# A7_FUNCTION3.net
KiCad netlist of a schematic drawn in Altium Designer
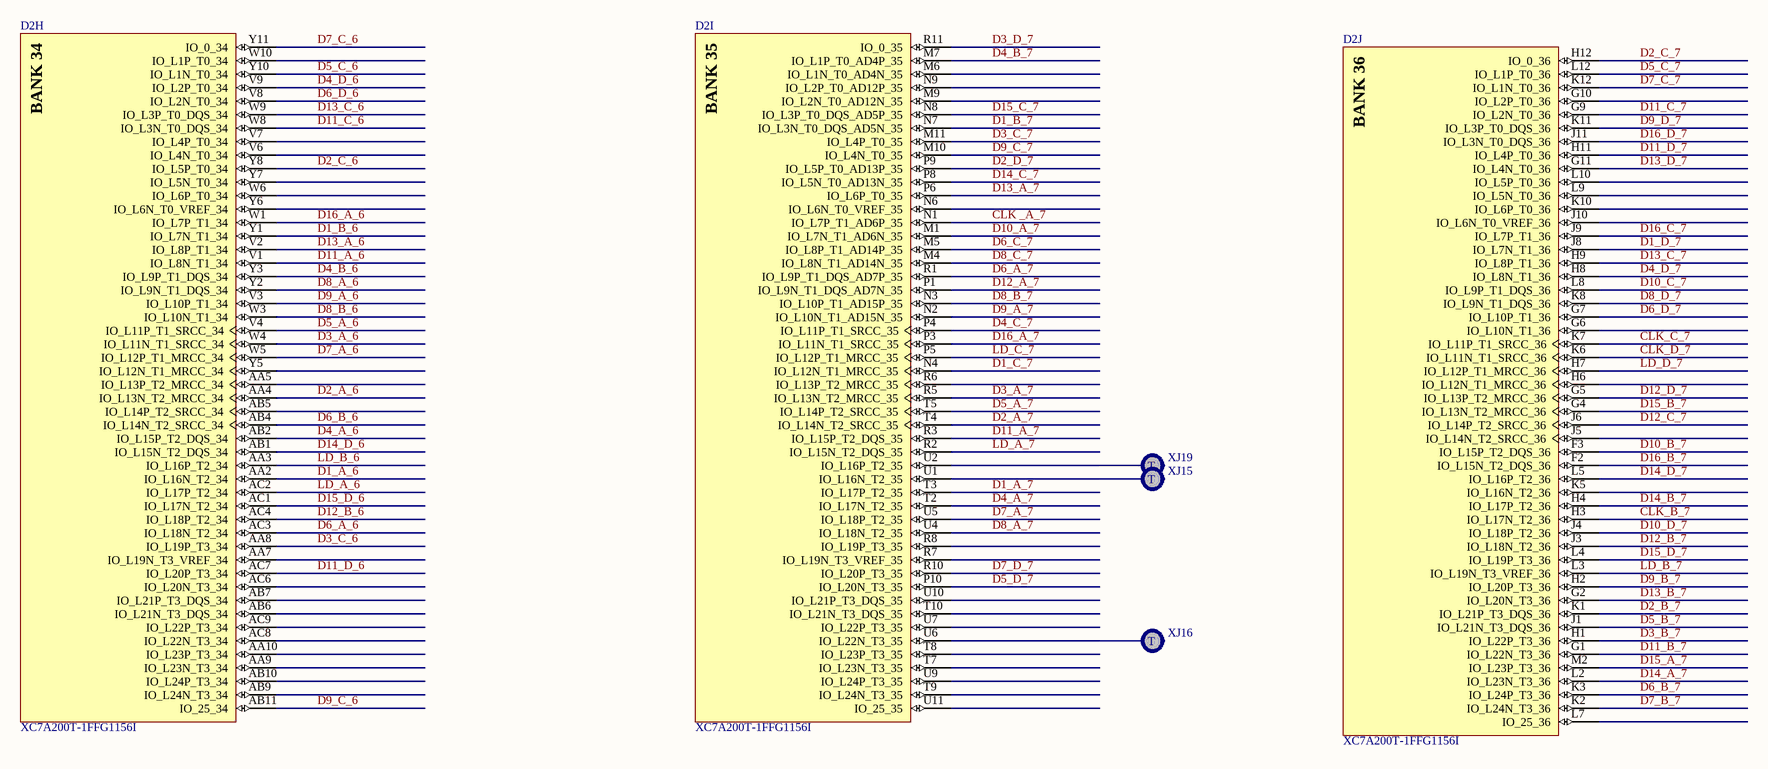
[diagram p0: A7_FUNCTION3.SchDoc]

(export (version "E")
  (design (tool "Eeschema 10.0.6"))
  (components
    (comp (ref "D2")
      (value "XC7A200T-1FFG1156I")
      (footprint "FFG1156")
      (description "Artix-7 FPGA, 500 User I/Os, 16 GTP, 1156-Ball BGA, Speed Grade 1, Industrial Grade, Pb-Free")
      (fields (field (name "GENERIC PART NUMBER") "XC7A200T") (field (name "MANUFACTURER") "Xilinx"))
      (libsource (lib "Xilinx Artix-7") (part "XC7A200T-1FFG1156I"))
    )
    (comp (ref "XJ15")
      (value "TESTPOINT")
      (footprint "TEST-pin")
      (description "测试点")
      (libsource (lib "Database_Libs1") (part "TESTPOINT"))
    )
    (comp (ref "XJ16")
      (value "TESTPOINT")
      (footprint "TEST-pin")
      (description "测试点")
      (libsource (lib "Database_Libs1") (part "TESTPOINT"))
    )
    (comp (ref "XJ19")
      (value "TESTPOINT")
      (footprint "TEST-pin")
      (description "测试点")
      (libsource (lib "Database_Libs1") (part "TESTPOINT"))
    )
  )
  (nets
    (net (code "1") (name "/CLK _A_7") (class "Default")
      (node (ref "D2") (pin "N1") (pinfunction "IO_L7P_T1_AD6P_35_N1") (pintype "bidirectional"))
    )
    (net (code "2") (name "/CLK_B_7") (class "Default")
      (node (ref "D2") (pin "H3") (pinfunction "IO_L17N_T2_36_H3") (pintype "bidirectional"))
    )
    (net (code "3") (name "/CLK_C_7") (class "Default")
      (node (ref "D2") (pin "K7") (pinfunction "IO_L11P_T1_SRCC_36_K7") (pintype "bidirectional"))
    )
    (net (code "4") (name "/CLK_D_7") (class "Default")
      (node (ref "D2") (pin "K6") (pinfunction "IO_L11N_T1_SRCC_36_K6") (pintype "bidirectional"))
    )
    (net (code "5") (name "/D1_A_6") (class "Default")
      (node (ref "D2") (pin "AA2") (pinfunction "IO_L16N_T2_34_AA2") (pintype "bidirectional"))
    )
    (net (code "6") (name "/D1_A_7") (class "Default")
      (node (ref "D2") (pin "T3") (pinfunction "IO_L17P_T2_35_T3") (pintype "bidirectional"))
    )
    (net (code "7") (name "/D1_B_6") (class "Default")
      (node (ref "D2") (pin "Y1") (pinfunction "IO_L7N_T1_34_Y1") (pintype "bidirectional"))
    )
    (net (code "8") (name "/D1_B_7") (class "Default")
      (node (ref "D2") (pin "N7") (pinfunction "IO_L3N_T0_DQS_AD5N_35_N7") (pintype "bidirectional"))
    )
    (net (code "9") (name "/D1_C_7") (class "Default")
      (node (ref "D2") (pin "N4") (pinfunction "IO_L12N_T1_MRCC_35_N4") (pintype "bidirectional"))
    )
    (net (code "10") (name "/D1_D_7") (class "Default")
      (node (ref "D2") (pin "J8") (pinfunction "IO_L7N_T1_36_J8") (pintype "bidirectional"))
    )
    (net (code "11") (name "/D2_A_6") (class "Default")
      (node (ref "D2") (pin "AA4") (pinfunction "IO_L13N_T2_MRCC_34_AA4") (pintype "bidirectional"))
    )
    (net (code "12") (name "/D2_A_7") (class "Default")
      (node (ref "D2") (pin "T4") (pinfunction "IO_L14N_T2_SRCC_35_T4") (pintype "bidirectional"))
    )
    (net (code "13") (name "/D2_B_7") (class "Default")
      (node (ref "D2") (pin "K1") (pinfunction "IO_L21P_T3_DQS_36_K1") (pintype "bidirectional"))
    )
    (net (code "14") (name "/D2_C_6") (class "Default")
      (node (ref "D2") (pin "Y8") (pinfunction "IO_L5P_T0_34_Y8") (pintype "bidirectional"))
    )
    (net (code "15") (name "/D2_C_7") (class "Default")
      (node (ref "D2") (pin "H12") (pinfunction "IO_0_36_H12") (pintype "bidirectional"))
    )
    (net (code "16") (name "/D2_D_7") (class "Default")
      (node (ref "D2") (pin "P9") (pinfunction "IO_L5P_T0_AD13P_35_P9") (pintype "bidirectional"))
    )
    (net (code "17") (name "/D3_A_6") (class "Default")
      (node (ref "D2") (pin "W4") (pinfunction "IO_L11N_T1_SRCC_34_W4") (pintype "bidirectional"))
    )
    (net (code "18") (name "/D3_A_7") (class "Default")
      (node (ref "D2") (pin "R5") (pinfunction "IO_L13N_T2_MRCC_35_R5") (pintype "bidirectional"))
    )
    (net (code "19") (name "/D3_B_7") (class "Default")
      (node (ref "D2") (pin "H1") (pinfunction "IO_L22P_T3_36_H1") (pintype "bidirectional"))
    )
    (net (code "20") (name "/D3_C_6") (class "Default")
      (node (ref "D2") (pin "AA8") (pinfunction "IO_L19P_T3_34_AA8") (pintype "bidirectional"))
    )
    (net (code "21") (name "/D3_C_7") (class "Default")
      (node (ref "D2") (pin "M11") (pinfunction "IO_L4P_T0_35_M11") (pintype "bidirectional"))
    )
    (net (code "22") (name "/D3_D_7") (class "Default")
      (node (ref "D2") (pin "R11") (pinfunction "IO_0_35_R11") (pintype "bidirectional"))
    )
    (net (code "23") (name "/D4_A_6") (class "Default")
      (node (ref "D2") (pin "AB2") (pinfunction "IO_L15P_T2_DQS_34_AB2") (pintype "bidirectional"))
    )
    (net (code "24") (name "/D4_A_7") (class "Default")
      (node (ref "D2") (pin "T2") (pinfunction "IO_L17N_T2_35_T2") (pintype "bidirectional"))
    )
    (net (code "25") (name "/D4_B_6") (class "Default")
      (node (ref "D2") (pin "Y3") (pinfunction "IO_L9P_T1_DQS_34_Y3") (pintype "bidirectional"))
    )
    (net (code "26") (name "/D4_B_7") (class "Default")
      (node (ref "D2") (pin "M7") (pinfunction "IO_L1P_T0_AD4P_35_M7") (pintype "bidirectional"))
    )
    (net (code "27") (name "/D4_C_7") (class "Default")
      (node (ref "D2") (pin "P4") (pinfunction "IO_L11P_T1_SRCC_35_P4") (pintype "bidirectional"))
    )
    (net (code "28") (name "/D4_D_6") (class "Default")
      (node (ref "D2") (pin "V9") (pinfunction "IO_L2P_T0_34_V9") (pintype "bidirectional"))
    )
    (net (code "29") (name "/D4_D_7") (class "Default")
      (node (ref "D2") (pin "H8") (pinfunction "IO_L8N_T1_36_H8") (pintype "bidirectional"))
    )
    (net (code "30") (name "/D5_A_6") (class "Default")
      (node (ref "D2") (pin "V4") (pinfunction "IO_L11P_T1_SRCC_34_V4") (pintype "bidirectional"))
    )
    (net (code "31") (name "/D5_A_7") (class "Default")
      (node (ref "D2") (pin "T5") (pinfunction "IO_L14P_T2_SRCC_35_T5") (pintype "bidirectional"))
    )
    (net (code "32") (name "/D5_B_7") (class "Default")
      (node (ref "D2") (pin "J1") (pinfunction "IO_L21N_T3_DQS_36_J1") (pintype "bidirectional"))
    )
    (net (code "33") (name "/D5_C_6") (class "Default")
      (node (ref "D2") (pin "Y10") (pinfunction "IO_L1N_T0_34_Y10") (pintype "bidirectional"))
    )
    (net (code "34") (name "/D5_C_7") (class "Default")
      (node (ref "D2") (pin "L12") (pinfunction "IO_L1P_T0_36_L12") (pintype "bidirectional"))
    )
    (net (code "35") (name "/D5_D_7") (class "Default")
      (node (ref "D2") (pin "P10") (pinfunction "IO_L20N_T3_35_P10") (pintype "bidirectional"))
    )
    (net (code "36") (name "/D6_A_6") (class "Default")
      (node (ref "D2") (pin "AC3") (pinfunction "IO_L18N_T2_34_AC3") (pintype "bidirectional"))
    )
    (net (code "37") (name "/D6_A_7") (class "Default")
      (node (ref "D2") (pin "R1") (pinfunction "IO_L9P_T1_DQS_AD7P_35_R1") (pintype "bidirectional"))
    )
    (net (code "38") (name "/D6_B_6") (class "Default")
      (node (ref "D2") (pin "AB4") (pinfunction "IO_L14N_T2_SRCC_34_AB4") (pintype "bidirectional"))
    )
    (net (code "39") (name "/D6_B_7") (class "Default")
      (node (ref "D2") (pin "K3") (pinfunction "IO_L24P_T3_36_K3") (pintype "bidirectional"))
    )
    (net (code "40") (name "/D6_C_7") (class "Default")
      (node (ref "D2") (pin "M5") (pinfunction "IO_L8P_T1_AD14P_35_M5") (pintype "bidirectional"))
    )
    (net (code "41") (name "/D6_D_6") (class "Default")
      (node (ref "D2") (pin "V8") (pinfunction "IO_L2N_T0_34_V8") (pintype "bidirectional"))
    )
    (net (code "42") (name "/D6_D_7") (class "Default")
      (node (ref "D2") (pin "G7") (pinfunction "IO_L10P_T1_36_G7") (pintype "bidirectional"))
    )
    (net (code "43") (name "/D7_A_6") (class "Default")
      (node (ref "D2") (pin "W5") (pinfunction "IO_L12P_T1_MRCC_34_W5") (pintype "bidirectional"))
    )
    (net (code "44") (name "/D7_A_7") (class "Default")
      (node (ref "D2") (pin "U5") (pinfunction "IO_L18P_T2_35_U5") (pintype "bidirectional"))
    )
    (net (code "45") (name "/D7_B_7") (class "Default")
      (node (ref "D2") (pin "K2") (pinfunction "IO_L24N_T3_36_K2") (pintype "bidirectional"))
    )
    (net (code "46") (name "/D7_C_6") (class "Default")
      (node (ref "D2") (pin "Y11") (pinfunction "IO_0_34_Y11") (pintype "bidirectional"))
    )
    (net (code "47") (name "/D7_C_7") (class "Default")
      (node (ref "D2") (pin "K12") (pinfunction "IO_L1N_T0_36_K12") (pintype "bidirectional"))
    )
    (net (code "48") (name "/D7_D_7") (class "Default")
      (node (ref "D2") (pin "R10") (pinfunction "IO_L20P_T3_35_R10") (pintype "bidirectional"))
    )
    (net (code "49") (name "/D8_A_6") (class "Default")
      (node (ref "D2") (pin "Y2") (pinfunction "IO_L9N_T1_DQS_34_Y2") (pintype "bidirectional"))
    )
    (net (code "50") (name "/D8_A_7") (class "Default")
      (node (ref "D2") (pin "U4") (pinfunction "IO_L18N_T2_35_U4") (pintype "bidirectional"))
    )
    (net (code "51") (name "/D8_B_6") (class "Default")
      (node (ref "D2") (pin "W3") (pinfunction "IO_L10N_T1_34_W3") (pintype "bidirectional"))
    )
    (net (code "52") (name "/D8_B_7") (class "Default")
      (node (ref "D2") (pin "N3") (pinfunction "IO_L10P_T1_AD15P_35_N3") (pintype "bidirectional"))
    )
    (net (code "53") (name "/D8_C_7") (class "Default")
      (node (ref "D2") (pin "M4") (pinfunction "IO_L8N_T1_AD14N_35_M4") (pintype "bidirectional"))
    )
    (net (code "54") (name "/D8_D_7") (class "Default")
      (node (ref "D2") (pin "K8") (pinfunction "IO_L9N_T1_DQS_36_K8") (pintype "bidirectional"))
    )
    (net (code "55") (name "/D9_A_6") (class "Default")
      (node (ref "D2") (pin "V3") (pinfunction "IO_L10P_T1_34_V3") (pintype "bidirectional"))
    )
    (net (code "56") (name "/D9_A_7") (class "Default")
      (node (ref "D2") (pin "N2") (pinfunction "IO_L10N_T1_AD15N_35_N2") (pintype "bidirectional"))
    )
    (net (code "57") (name "/D9_B_7") (class "Default")
      (node (ref "D2") (pin "H2") (pinfunction "IO_L20P_T3_36_H2") (pintype "bidirectional"))
    )
    (net (code "58") (name "/D9_C_6") (class "Default")
      (node (ref "D2") (pin "AB11") (pinfunction "IO_25_34_AB11") (pintype "bidirectional"))
    )
    (net (code "59") (name "/D9_C_7") (class "Default")
      (node (ref "D2") (pin "M10") (pinfunction "IO_L4N_T0_35_M10") (pintype "bidirectional"))
    )
    (net (code "60") (name "/D9_D_7") (class "Default")
      (node (ref "D2") (pin "K11") (pinfunction "IO_L3P_T0_DQS_36_K11") (pintype "bidirectional"))
    )
    (net (code "61") (name "/D10_A_7") (class "Default")
      (node (ref "D2") (pin "M1") (pinfunction "IO_L7N_T1_AD6N_35_M1") (pintype "bidirectional"))
    )
    (net (code "62") (name "/D10_B_7") (class "Default")
      (node (ref "D2") (pin "F3") (pinfunction "IO_L15P_T2_DQS_36_F3") (pintype "bidirectional"))
    )
    (net (code "63") (name "/D10_C_7") (class "Default")
      (node (ref "D2") (pin "L8") (pinfunction "IO_L9P_T1_DQS_36_L8") (pintype "bidirectional"))
    )
    (net (code "64") (name "/D10_D_7") (class "Default")
      (node (ref "D2") (pin "J4") (pinfunction "IO_L18P_T2_36_J4") (pintype "bidirectional"))
    )
    (net (code "65") (name "/D11_A_6") (class "Default")
      (node (ref "D2") (pin "V1") (pinfunction "IO_L8N_T1_34_V1") (pintype "bidirectional"))
    )
    (net (code "66") (name "/D11_A_7") (class "Default")
      (node (ref "D2") (pin "R3") (pinfunction "IO_L15P_T2_DQS_35_R3") (pintype "bidirectional"))
    )
    (net (code "67") (name "/D11_B_7") (class "Default")
      (node (ref "D2") (pin "G1") (pinfunction "IO_L22N_T3_36_G1") (pintype "bidirectional"))
    )
    (net (code "68") (name "/D11_C_6") (class "Default")
      (node (ref "D2") (pin "W8") (pinfunction "IO_L3N_T0_DQS_34_W8") (pintype "bidirectional"))
    )
    (net (code "69") (name "/D11_C_7") (class "Default")
      (node (ref "D2") (pin "G9") (pinfunction "IO_L2N_T0_36_G9") (pintype "bidirectional"))
    )
    (net (code "70") (name "/D11_D_6") (class "Default")
      (node (ref "D2") (pin "AC7") (pinfunction "IO_L20P_T3_34_AC7") (pintype "bidirectional"))
    )
    (net (code "71") (name "/D11_D_7") (class "Default")
      (node (ref "D2") (pin "H11") (pinfunction "IO_L4P_T0_36_H11") (pintype "bidirectional"))
    )
    (net (code "72") (name "/D12_A_7") (class "Default")
      (node (ref "D2") (pin "P1") (pinfunction "IO_L9N_T1_DQS_AD7N_35_P1") (pintype "bidirectional"))
    )
    (net (code "73") (name "/D12_B_6") (class "Default")
      (node (ref "D2") (pin "AC4") (pinfunction "IO_L18P_T2_34_AC4") (pintype "bidirectional"))
    )
    (net (code "74") (name "/D12_B_7") (class "Default")
      (node (ref "D2") (pin "J3") (pinfunction "IO_L18N_T2_36_J3") (pintype "bidirectional"))
    )
    (net (code "75") (name "/D12_C_7") (class "Default")
      (node (ref "D2") (pin "J6") (pinfunction "IO_L14P_T2_SRCC_36_J6") (pintype "bidirectional"))
    )
    (net (code "76") (name "/D12_D_7") (class "Default")
      (node (ref "D2") (pin "G5") (pinfunction "IO_L13P_T2_MRCC_36_G5") (pintype "bidirectional"))
    )
    (net (code "77") (name "/D13_A_6") (class "Default")
      (node (ref "D2") (pin "V2") (pinfunction "IO_L8P_T1_34_V2") (pintype "bidirectional"))
    )
    (net (code "78") (name "/D13_A_7") (class "Default")
      (node (ref "D2") (pin "P6") (pinfunction "IO_L6P_T0_35_P6") (pintype "bidirectional"))
    )
    (net (code "79") (name "/D13_B_7") (class "Default")
      (node (ref "D2") (pin "G2") (pinfunction "IO_L20N_T3_36_G2") (pintype "bidirectional"))
    )
    (net (code "80") (name "/D13_C_6") (class "Default")
      (node (ref "D2") (pin "W9") (pinfunction "IO_L3P_T0_DQS_34_W9") (pintype "bidirectional"))
    )
    (net (code "81") (name "/D13_C_7") (class "Default")
      (node (ref "D2") (pin "H9") (pinfunction "IO_L8P_T1_36_H9") (pintype "bidirectional"))
    )
    (net (code "82") (name "/D13_D_7") (class "Default")
      (node (ref "D2") (pin "G11") (pinfunction "IO_L4N_T0_36_G11") (pintype "bidirectional"))
    )
    (net (code "83") (name "/D14_A_7") (class "Default")
      (node (ref "D2") (pin "L2") (pinfunction "IO_L23N_T3_36_L2") (pintype "bidirectional"))
    )
    (net (code "84") (name "/D14_B_7") (class "Default")
      (node (ref "D2") (pin "H4") (pinfunction "IO_L17P_T2_36_H4") (pintype "bidirectional"))
    )
    (net (code "85") (name "/D14_C_7") (class "Default")
      (node (ref "D2") (pin "P8") (pinfunction "IO_L5N_T0_AD13N_35_P8") (pintype "bidirectional"))
    )
    (net (code "86") (name "/D14_D_6") (class "Default")
      (node (ref "D2") (pin "AB1") (pinfunction "IO_L15N_T2_DQS_34_AB1") (pintype "bidirectional"))
    )
    (net (code "87") (name "/D14_D_7") (class "Default")
      (node (ref "D2") (pin "L5") (pinfunction "IO_L16P_T2_36_L5") (pintype "bidirectional"))
    )
    (net (code "88") (name "/D15_A_7") (class "Default")
      (node (ref "D2") (pin "M2") (pinfunction "IO_L23P_T3_36_M2") (pintype "bidirectional"))
    )
    (net (code "89") (name "/D15_B_7") (class "Default")
      (node (ref "D2") (pin "G4") (pinfunction "IO_L13N_T2_MRCC_36_G4") (pintype "bidirectional"))
    )
    (net (code "90") (name "/D15_C_7") (class "Default")
      (node (ref "D2") (pin "N8") (pinfunction "IO_L3P_T0_DQS_AD5P_35_N8") (pintype "bidirectional"))
    )
    (net (code "91") (name "/D15_D_6") (class "Default")
      (node (ref "D2") (pin "AC1") (pinfunction "IO_L17N_T2_34_AC1") (pintype "bidirectional"))
    )
    (net (code "92") (name "/D15_D_7") (class "Default")
      (node (ref "D2") (pin "L4") (pinfunction "IO_L19P_T3_36_L4") (pintype "bidirectional"))
    )
    (net (code "93") (name "/D16_A_6") (class "Default")
      (node (ref "D2") (pin "W1") (pinfunction "IO_L7P_T1_34_W1") (pintype "bidirectional"))
    )
    (net (code "94") (name "/D16_A_7") (class "Default")
      (node (ref "D2") (pin "P3") (pinfunction "IO_L11N_T1_SRCC_35_P3") (pintype "bidirectional"))
    )
    (net (code "95") (name "/D16_B_7") (class "Default")
      (node (ref "D2") (pin "F2") (pinfunction "IO_L15N_T2_DQS_36_F2") (pintype "bidirectional"))
    )
    (net (code "96") (name "/D16_C_7") (class "Default")
      (node (ref "D2") (pin "J9") (pinfunction "IO_L7P_T1_36_J9") (pintype "bidirectional"))
    )
    (net (code "97") (name "/D16_D_7") (class "Default")
      (node (ref "D2") (pin "J11") (pinfunction "IO_L3N_T0_DQS_36_J11") (pintype "bidirectional"))
    )
    (net (code "98") (name "/LD_A_6") (class "Default")
      (node (ref "D2") (pin "AC2") (pinfunction "IO_L17P_T2_34_AC2") (pintype "bidirectional"))
    )
    (net (code "99") (name "/LD_A_7") (class "Default")
      (node (ref "D2") (pin "R2") (pinfunction "IO_L15N_T2_DQS_35_R2") (pintype "bidirectional"))
    )
    (net (code "100") (name "/LD_B_6") (class "Default")
      (node (ref "D2") (pin "AA3") (pinfunction "IO_L16P_T2_34_AA3") (pintype "bidirectional"))
    )
    (net (code "101") (name "/LD_B_7") (class "Default")
      (node (ref "D2") (pin "L3") (pinfunction "IO_L19N_T3_VREF_36_L3") (pintype "bidirectional"))
    )
    (net (code "102") (name "/LD_C_7") (class "Default")
      (node (ref "D2") (pin "P5") (pinfunction "IO_L12P_T1_MRCC_35_P5") (pintype "bidirectional"))
    )
    (net (code "103") (name "/LD_D_7") (class "Default")
      (node (ref "D2") (pin "H7") (pinfunction "IO_L12P_T1_MRCC_36_H7") (pintype "bidirectional"))
    )
    (net (code "104") (name "Net-(D2I-IO_L16N_T2_35)") (class "Default")
      (node (ref "D2") (pin "U1") (pinfunction "IO_L16N_T2_35_U1") (pintype "bidirectional"))
      (node (ref "XJ15") (pin "1") (pinfunction "T_1") (pintype "passive"))
    )
    (net (code "105") (name "Net-(D2I-IO_L16P_T2_35)") (class "Default")
      (node (ref "D2") (pin "U2") (pinfunction "IO_L16P_T2_35_U2") (pintype "bidirectional"))
      (node (ref "XJ19") (pin "1") (pinfunction "T_1") (pintype "passive"))
    )
    (net (code "106") (name "Net-(D2I-IO_L22N_T3_35)") (class "Default")
      (node (ref "D2") (pin "U6") (pinfunction "IO_L22N_T3_35_U6") (pintype "bidirectional"))
      (node (ref "XJ16") (pin "1") (pinfunction "T_1") (pintype "passive"))
    )
    (net (code "107") (name "unconnected-(D2H-IO_L1P_T0_34-PadW10)") (class "Default")
      (node (ref "D2") (pin "W10") (pinfunction "IO_L1P_T0_34_W10") (pintype "bidirectional"))
    )
    (net (code "108") (name "unconnected-(D2H-IO_L4N_T0_34-PadV6)") (class "Default")
      (node (ref "D2") (pin "V6") (pinfunction "IO_L4N_T0_34_V6") (pintype "bidirectional"))
    )
    (net (code "109") (name "unconnected-(D2H-IO_L4P_T0_34-PadV7)") (class "Default")
      (node (ref "D2") (pin "V7") (pinfunction "IO_L4P_T0_34_V7") (pintype "bidirectional"))
    )
    (net (code "110") (name "unconnected-(D2H-IO_L5N_T0_34-PadY7)") (class "Default")
      (node (ref "D2") (pin "Y7") (pinfunction "IO_L5N_T0_34_Y7") (pintype "bidirectional"))
    )
    (net (code "111") (name "unconnected-(D2H-IO_L6N_T0_VREF_34-PadY6)") (class "Default")
      (node (ref "D2") (pin "Y6") (pinfunction "IO_L6N_T0_VREF_34_Y6") (pintype "bidirectional"))
    )
    (net (code "112") (name "unconnected-(D2H-IO_L6P_T0_34-PadW6)") (class "Default")
      (node (ref "D2") (pin "W6") (pinfunction "IO_L6P_T0_34_W6") (pintype "bidirectional"))
    )
    (net (code "113") (name "unconnected-(D2H-IO_L12N_T1_MRCC_34-PadY5)") (class "Default")
      (node (ref "D2") (pin "Y5") (pinfunction "IO_L12N_T1_MRCC_34_Y5") (pintype "bidirectional"))
    )
    (net (code "114") (name "unconnected-(D2H-IO_L13P_T2_MRCC_34-PadAA5)") (class "Default")
      (node (ref "D2") (pin "AA5") (pinfunction "IO_L13P_T2_MRCC_34_AA5") (pintype "bidirectional"))
    )
    (net (code "115") (name "unconnected-(D2H-IO_L14P_T2_SRCC_34-PadAB5)") (class "Default")
      (node (ref "D2") (pin "AB5") (pinfunction "IO_L14P_T2_SRCC_34_AB5") (pintype "bidirectional"))
    )
    (net (code "116") (name "unconnected-(D2H-IO_L19N_T3_VREF_34-PadAA7)") (class "Default")
      (node (ref "D2") (pin "AA7") (pinfunction "IO_L19N_T3_VREF_34_AA7") (pintype "bidirectional"))
    )
    (net (code "117") (name "unconnected-(D2H-IO_L20N_T3_34-PadAC6)") (class "Default")
      (node (ref "D2") (pin "AC6") (pinfunction "IO_L20N_T3_34_AC6") (pintype "bidirectional"))
    )
    (net (code "118") (name "unconnected-(D2H-IO_L21N_T3_DQS_34-PadAB6)") (class "Default")
      (node (ref "D2") (pin "AB6") (pinfunction "IO_L21N_T3_DQS_34_AB6") (pintype "bidirectional"))
    )
    (net (code "119") (name "unconnected-(D2H-IO_L21P_T3_DQS_34-PadAB7)") (class "Default")
      (node (ref "D2") (pin "AB7") (pinfunction "IO_L21P_T3_DQS_34_AB7") (pintype "bidirectional"))
    )
    (net (code "120") (name "unconnected-(D2H-IO_L22N_T3_34-PadAC8)") (class "Default")
      (node (ref "D2") (pin "AC8") (pinfunction "IO_L22N_T3_34_AC8") (pintype "bidirectional"))
    )
    (net (code "121") (name "unconnected-(D2H-IO_L22P_T3_34-PadAC9)") (class "Default")
      (node (ref "D2") (pin "AC9") (pinfunction "IO_L22P_T3_34_AC9") (pintype "bidirectional"))
    )
    (net (code "122") (name "unconnected-(D2H-IO_L23N_T3_34-PadAA9)") (class "Default")
      (node (ref "D2") (pin "AA9") (pinfunction "IO_L23N_T3_34_AA9") (pintype "bidirectional"))
    )
    (net (code "123") (name "unconnected-(D2H-IO_L23P_T3_34-PadAA10)") (class "Default")
      (node (ref "D2") (pin "AA10") (pinfunction "IO_L23P_T3_34_AA10") (pintype "bidirectional"))
    )
    (net (code "124") (name "unconnected-(D2H-IO_L24N_T3_34-PadAB9)") (class "Default")
      (node (ref "D2") (pin "AB9") (pinfunction "IO_L24N_T3_34_AB9") (pintype "bidirectional"))
    )
    (net (code "125") (name "unconnected-(D2H-IO_L24P_T3_34-PadAB10)") (class "Default")
      (node (ref "D2") (pin "AB10") (pinfunction "IO_L24P_T3_34_AB10") (pintype "bidirectional"))
    )
    (net (code "126") (name "unconnected-(D2I-IO_25_35-PadU11)") (class "Default")
      (node (ref "D2") (pin "U11") (pinfunction "IO_25_35_U11") (pintype "bidirectional"))
    )
    (net (code "127") (name "unconnected-(D2I-IO_L1N_T0_AD4N_35-PadM6)") (class "Default")
      (node (ref "D2") (pin "M6") (pinfunction "IO_L1N_T0_AD4N_35_M6") (pintype "bidirectional"))
    )
    (net (code "128") (name "unconnected-(D2I-IO_L2N_T0_AD12N_35-PadM9)") (class "Default")
      (node (ref "D2") (pin "M9") (pinfunction "IO_L2N_T0_AD12N_35_M9") (pintype "bidirectional"))
    )
    (net (code "129") (name "unconnected-(D2I-IO_L2P_T0_AD12P_35-PadN9)") (class "Default")
      (node (ref "D2") (pin "N9") (pinfunction "IO_L2P_T0_AD12P_35_N9") (pintype "bidirectional"))
    )
    (net (code "130") (name "unconnected-(D2I-IO_L6N_T0_VREF_35-PadN6)") (class "Default")
      (node (ref "D2") (pin "N6") (pinfunction "IO_L6N_T0_VREF_35_N6") (pintype "bidirectional"))
    )
    (net (code "131") (name "unconnected-(D2I-IO_L13P_T2_MRCC_35-PadR6)") (class "Default")
      (node (ref "D2") (pin "R6") (pinfunction "IO_L13P_T2_MRCC_35_R6") (pintype "bidirectional"))
    )
    (net (code "132") (name "unconnected-(D2I-IO_L19N_T3_VREF_35-PadR7)") (class "Default")
      (node (ref "D2") (pin "R7") (pinfunction "IO_L19N_T3_VREF_35_R7") (pintype "bidirectional"))
    )
    (net (code "133") (name "unconnected-(D2I-IO_L19P_T3_35-PadR8)") (class "Default")
      (node (ref "D2") (pin "R8") (pinfunction "IO_L19P_T3_35_R8") (pintype "bidirectional"))
    )
    (net (code "134") (name "unconnected-(D2I-IO_L21N_T3_DQS_35-PadT10)") (class "Default")
      (node (ref "D2") (pin "T10") (pinfunction "IO_L21N_T3_DQS_35_T10") (pintype "bidirectional"))
    )
    (net (code "135") (name "unconnected-(D2I-IO_L21P_T3_DQS_35-PadU10)") (class "Default")
      (node (ref "D2") (pin "U10") (pinfunction "IO_L21P_T3_DQS_35_U10") (pintype "bidirectional"))
    )
    (net (code "136") (name "unconnected-(D2I-IO_L22P_T3_35-PadU7)") (class "Default")
      (node (ref "D2") (pin "U7") (pinfunction "IO_L22P_T3_35_U7") (pintype "bidirectional"))
    )
    (net (code "137") (name "unconnected-(D2I-IO_L23N_T3_35-PadT7)") (class "Default")
      (node (ref "D2") (pin "T7") (pinfunction "IO_L23N_T3_35_T7") (pintype "bidirectional"))
    )
    (net (code "138") (name "unconnected-(D2I-IO_L23P_T3_35-PadT8)") (class "Default")
      (node (ref "D2") (pin "T8") (pinfunction "IO_L23P_T3_35_T8") (pintype "bidirectional"))
    )
    (net (code "139") (name "unconnected-(D2I-IO_L24N_T3_35-PadT9)") (class "Default")
      (node (ref "D2") (pin "T9") (pinfunction "IO_L24N_T3_35_T9") (pintype "bidirectional"))
    )
    (net (code "140") (name "unconnected-(D2I-IO_L24P_T3_35-PadU9)") (class "Default")
      (node (ref "D2") (pin "U9") (pinfunction "IO_L24P_T3_35_U9") (pintype "bidirectional"))
    )
    (net (code "141") (name "unconnected-(D2J-IO_25_36-PadL7)") (class "Default")
      (node (ref "D2") (pin "L7") (pinfunction "IO_25_36_L7") (pintype "bidirectional"))
    )
    (net (code "142") (name "unconnected-(D2J-IO_L2P_T0_36-PadG10)") (class "Default")
      (node (ref "D2") (pin "G10") (pinfunction "IO_L2P_T0_36_G10") (pintype "bidirectional"))
    )
    (net (code "143") (name "unconnected-(D2J-IO_L5N_T0_36-PadL9)") (class "Default")
      (node (ref "D2") (pin "L9") (pinfunction "IO_L5N_T0_36_L9") (pintype "bidirectional"))
    )
    (net (code "144") (name "unconnected-(D2J-IO_L5P_T0_36-PadL10)") (class "Default")
      (node (ref "D2") (pin "L10") (pinfunction "IO_L5P_T0_36_L10") (pintype "bidirectional"))
    )
    (net (code "145") (name "unconnected-(D2J-IO_L6N_T0_VREF_36-PadJ10)") (class "Default")
      (node (ref "D2") (pin "J10") (pinfunction "IO_L6N_T0_VREF_36_J10") (pintype "bidirectional"))
    )
    (net (code "146") (name "unconnected-(D2J-IO_L6P_T0_36-PadK10)") (class "Default")
      (node (ref "D2") (pin "K10") (pinfunction "IO_L6P_T0_36_K10") (pintype "bidirectional"))
    )
    (net (code "147") (name "unconnected-(D2J-IO_L10N_T1_36-PadG6)") (class "Default")
      (node (ref "D2") (pin "G6") (pinfunction "IO_L10N_T1_36_G6") (pintype "bidirectional"))
    )
    (net (code "148") (name "unconnected-(D2J-IO_L12N_T1_MRCC_36-PadH6)") (class "Default")
      (node (ref "D2") (pin "H6") (pinfunction "IO_L12N_T1_MRCC_36_H6") (pintype "bidirectional"))
    )
    (net (code "149") (name "unconnected-(D2J-IO_L14N_T2_SRCC_36-PadJ5)") (class "Default")
      (node (ref "D2") (pin "J5") (pinfunction "IO_L14N_T2_SRCC_36_J5") (pintype "bidirectional"))
    )
    (net (code "150") (name "unconnected-(D2J-IO_L16N_T2_36-PadK5)") (class "Default")
      (node (ref "D2") (pin "K5") (pinfunction "IO_L16N_T2_36_K5") (pintype "bidirectional"))
    )
  )
)
